# SPV_PCB_uzd_1.net
KiCad netlist of a schematic drawn in EAGLE
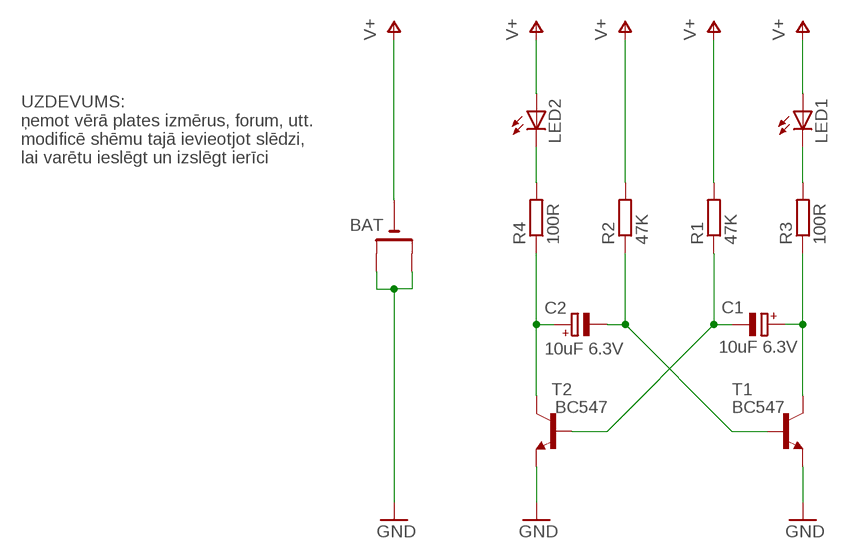
[diagram p0: schematic, sheet 1]

(export (version "E")
  (design (tool "Eeschema 10.0.6"))
  (components
    (comp (ref "BAT")
      (value "CR2032THM")
      (footprint "eagle-import:CR2032-THRU")
      (libsource (lib "eagle-import") (part "CR2032THM"))
    )
    (comp (ref "C1")
      (value "10uF 6.3V")
      (footprint "eagle-import:E1,8-4")
      (libsource (lib "eagle-import") (part "CAP_POL_4MMCAP_POL"))
    )
    (comp (ref "C2")
      (value "10uF 6.3V")
      (footprint "eagle-import:E1,8-4")
      (libsource (lib "eagle-import") (part "CAP_POL_4MMCAP_POL"))
    )
    (comp (ref "LED1")
      (value "LED5MM")
      (footprint "eagle-import:LED5MM")
      (libsource (lib "eagle-import") (part "LED5MM"))
    )
    (comp (ref "LED2")
      (value "LED5MM")
      (footprint "eagle-import:LED5MM")
      (libsource (lib "eagle-import") (part "LED5MM"))
    )
    (comp (ref "R1")
      (value "47K")
      (footprint "eagle-import:R-7.5MM")
      (libsource (lib "eagle-import") (part "RESISTOR_7.5MM_HORIZONTAL"))
    )
    (comp (ref "R2")
      (value "47K")
      (footprint "eagle-import:R-7.5MM")
      (libsource (lib "eagle-import") (part "RESISTOR_7.5MM_HORIZONTAL"))
    )
    (comp (ref "R3")
      (value "100R")
      (footprint "eagle-import:R-7.5MM")
      (libsource (lib "eagle-import") (part "RESISTOR_7.5MM_HORIZONTAL"))
    )
    (comp (ref "R4")
      (value "100R")
      (footprint "eagle-import:R-7.5MM")
      (libsource (lib "eagle-import") (part "RESISTOR_7.5MM_HORIZONTAL"))
    )
    (comp (ref "T1")
      (value "BC547")
      (footprint "eagle-import:TO92")
      (libsource (lib "eagle-import") (part "BC547"))
    )
    (comp (ref "T2")
      (value "BC547")
      (footprint "eagle-import:TO92")
      (libsource (lib "eagle-import") (part "BC547"))
    )
  )
  (nets
    (net (code "1") (name "GND") (class "Default")
      (node (ref "BAT") (pin "+1") (pinfunction "+_+1") (pintype "passive"))
      (node (ref "BAT") (pin "+2") (pinfunction "+1_+2") (pintype "passive"))
      (node (ref "T1") (pin "1") (pinfunction "E_1") (pintype "passive"))
      (node (ref "T2") (pin "1") (pinfunction "E_1") (pintype "passive"))
    )
    (net (code "2") (name "Net-(LED1-C)") (class "Default")
      (node (ref "LED1") (pin "K") (pinfunction "C_K") (pintype "passive"))
      (node (ref "R3") (pin "2") (pinfunction "2_2") (pintype "passive"))
    )
    (net (code "3") (name "Net-(LED2-C)") (class "Default")
      (node (ref "LED2") (pin "K") (pinfunction "C_K") (pintype "passive"))
      (node (ref "R4") (pin "2") (pinfunction "2_2") (pintype "passive"))
    )
    (net (code "4") (name "Net-(T1-B)") (class "Default")
      (node (ref "C2") (pin "-") (pinfunction "-_-") (pintype "passive"))
      (node (ref "R2") (pin "1") (pinfunction "1_1") (pintype "passive"))
      (node (ref "T1") (pin "2") (pinfunction "B_2") (pintype "passive"))
    )
    (net (code "5") (name "Net-(T1-C)") (class "Default")
      (node (ref "C1") (pin "+") (pinfunction "+_+") (pintype "passive"))
      (node (ref "R3") (pin "1") (pinfunction "1_1") (pintype "passive"))
      (node (ref "T1") (pin "3") (pinfunction "C_3") (pintype "passive"))
    )
    (net (code "6") (name "Net-(T2-B)") (class "Default")
      (node (ref "C1") (pin "-") (pinfunction "-_-") (pintype "passive"))
      (node (ref "R1") (pin "1") (pinfunction "1_1") (pintype "passive"))
      (node (ref "T2") (pin "2") (pinfunction "B_2") (pintype "passive"))
    )
    (net (code "7") (name "Net-(T2-C)") (class "Default")
      (node (ref "C2") (pin "+") (pinfunction "+_+") (pintype "passive"))
      (node (ref "R4") (pin "1") (pinfunction "1_1") (pintype "passive"))
      (node (ref "T2") (pin "3") (pinfunction "C_3") (pintype "passive"))
    )
    (net (code "8") (name "V+") (class "Default")
      (node (ref "BAT") (pin "-") (pinfunction "-_-") (pintype "passive"))
      (node (ref "LED1") (pin "A") (pinfunction "A_A") (pintype "passive"))
      (node (ref "LED2") (pin "A") (pinfunction "A_A") (pintype "passive"))
      (node (ref "R1") (pin "2") (pinfunction "2_2") (pintype "passive"))
      (node (ref "R2") (pin "2") (pinfunction "2_2") (pintype "passive"))
    )
  )
)
